# eight_neopixels.net
KiCad netlist of a schematic drawn in Altium Designer
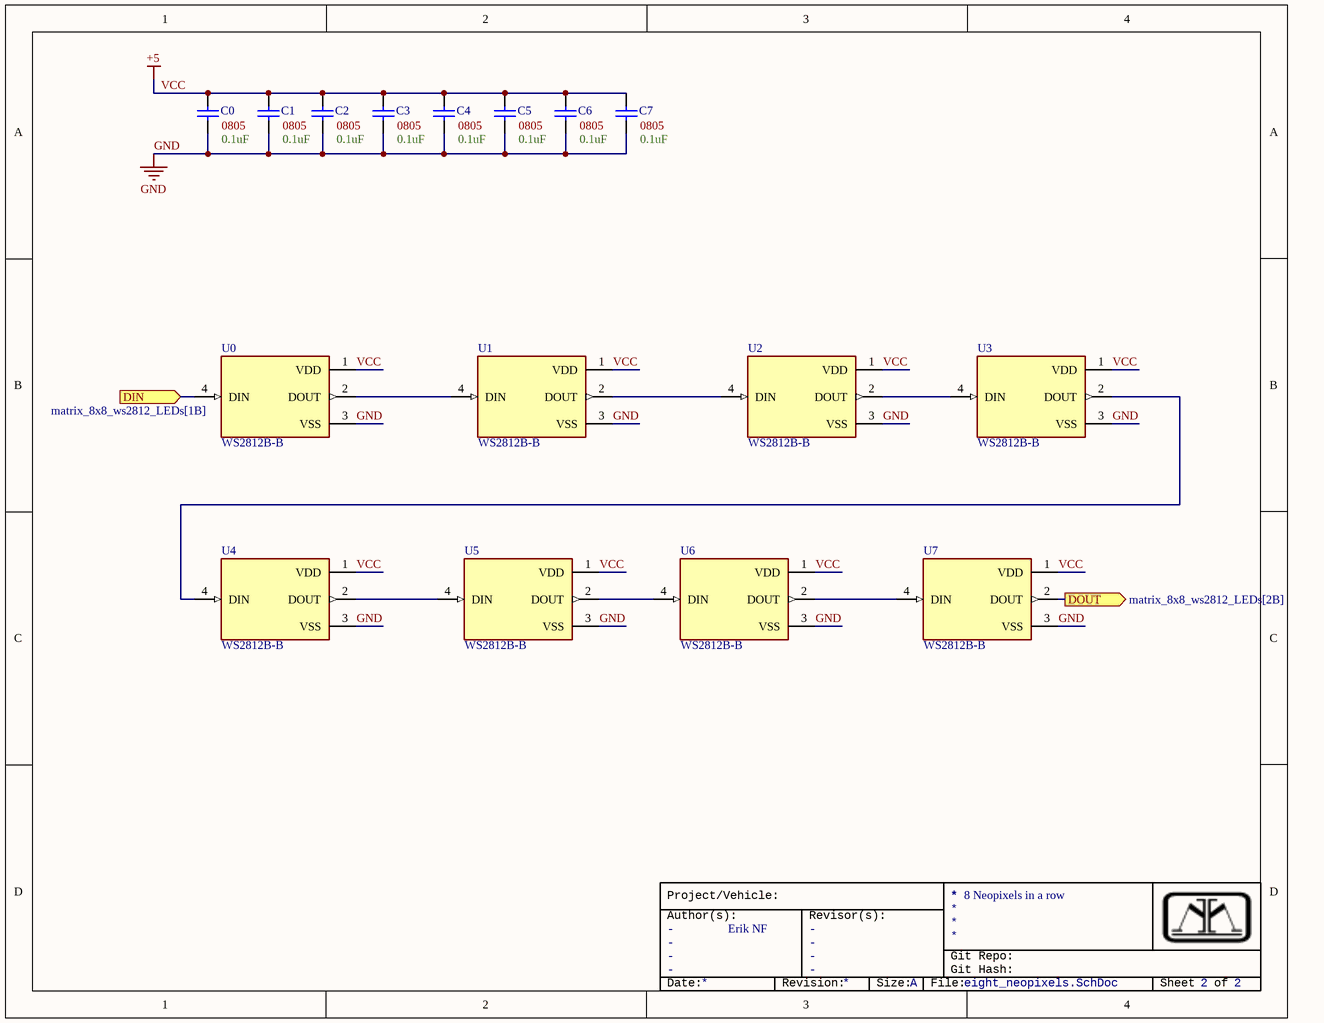
[diagram p0: eight_neopixels.SchDoc]

(export (version "E")
  (design (tool "Eeschema 10.0.6"))
  (components
    (comp (ref "C0")
      (value "SMD Nonpolarized")
      (footprint "[Cap] SMD 0805")
      (fields
        (field (name "VOLTAGE") "6.3V")
        (field (name "TOLERANCE") "10%")
        (field (name "SIZE PACKAGE") "0805")
        (field (name "CAPACITANCE") "0.1uF")
      )
      (libsource (lib "RADM Components") (part "[Cap] SMD Nonpolarized"))
    )
    (comp (ref "C1")
      (value "SMD Nonpolarized")
      (footprint "[Cap] SMD 0805")
      (fields
        (field (name "VOLTAGE") "6.3V")
        (field (name "TOLERANCE") "10%")
        (field (name "SIZE PACKAGE") "0805")
        (field (name "CAPACITANCE") "0.1uF")
      )
      (libsource (lib "RADM Components") (part "[Cap] SMD Nonpolarized"))
    )
    (comp (ref "C2")
      (value "SMD Nonpolarized")
      (footprint "[Cap] SMD 0805")
      (fields
        (field (name "VOLTAGE") "6.3V")
        (field (name "TOLERANCE") "10%")
        (field (name "SIZE PACKAGE") "0805")
        (field (name "CAPACITANCE") "0.1uF")
      )
      (libsource (lib "RADM Components") (part "[Cap] SMD Nonpolarized"))
    )
    (comp (ref "C3")
      (value "SMD Nonpolarized")
      (footprint "[Cap] SMD 0805")
      (fields
        (field (name "VOLTAGE") "6.3V")
        (field (name "TOLERANCE") "10%")
        (field (name "SIZE PACKAGE") "0805")
        (field (name "CAPACITANCE") "0.1uF")
      )
      (libsource (lib "RADM Components") (part "[Cap] SMD Nonpolarized"))
    )
    (comp (ref "C4")
      (value "SMD Nonpolarized")
      (footprint "[Cap] SMD 0805")
      (fields
        (field (name "VOLTAGE") "6.3V")
        (field (name "TOLERANCE") "10%")
        (field (name "SIZE PACKAGE") "0805")
        (field (name "CAPACITANCE") "0.1uF")
      )
      (libsource (lib "RADM Components") (part "[Cap] SMD Nonpolarized"))
    )
    (comp (ref "C5")
      (value "SMD Nonpolarized")
      (footprint "[Cap] SMD 0805")
      (fields
        (field (name "VOLTAGE") "6.3V")
        (field (name "TOLERANCE") "10%")
        (field (name "SIZE PACKAGE") "0805")
        (field (name "CAPACITANCE") "0.1uF")
      )
      (libsource (lib "RADM Components") (part "[Cap] SMD Nonpolarized"))
    )
    (comp (ref "C6")
      (value "SMD Nonpolarized")
      (footprint "[Cap] SMD 0805")
      (fields
        (field (name "VOLTAGE") "6.3V")
        (field (name "TOLERANCE") "10%")
        (field (name "SIZE PACKAGE") "0805")
        (field (name "CAPACITANCE") "0.1uF")
      )
      (libsource (lib "RADM Components") (part "[Cap] SMD Nonpolarized"))
    )
    (comp (ref "C7")
      (value "SMD Nonpolarized")
      (footprint "[Cap] SMD 0805")
      (fields
        (field (name "VOLTAGE") "6.3V")
        (field (name "TOLERANCE") "10%")
        (field (name "SIZE PACKAGE") "0805")
        (field (name "CAPACITANCE") "0.1uF")
      )
      (libsource (lib "RADM Components") (part "[Cap] SMD Nonpolarized"))
    )
    (comp (ref "U0")
      (value "WS2812B-B")
      (footprint "LED_WS2812B-B")
      (description "Intelligent control LED integrated light source")
      (libsource (lib "WS2812B-B") (part "WS2812B-B"))
    )
    (comp (ref "U1")
      (value "WS2812B-B")
      (footprint "LED_WS2812B-B")
      (description "Intelligent control LED integrated light source")
      (libsource (lib "WS2812B-B") (part "WS2812B-B"))
    )
    (comp (ref "U2")
      (value "WS2812B-B")
      (footprint "LED_WS2812B-B")
      (description "Intelligent control LED integrated light source")
      (libsource (lib "WS2812B-B") (part "WS2812B-B"))
    )
    (comp (ref "U3")
      (value "WS2812B-B")
      (footprint "LED_WS2812B-B")
      (description "Intelligent control LED integrated light source")
      (libsource (lib "WS2812B-B") (part "WS2812B-B"))
    )
    (comp (ref "U4")
      (value "WS2812B-B")
      (footprint "LED_WS2812B-B")
      (description "Intelligent control LED integrated light source")
      (libsource (lib "WS2812B-B") (part "WS2812B-B"))
    )
    (comp (ref "U5")
      (value "WS2812B-B")
      (footprint "LED_WS2812B-B")
      (description "Intelligent control LED integrated light source")
      (libsource (lib "WS2812B-B") (part "WS2812B-B"))
    )
    (comp (ref "U6")
      (value "WS2812B-B")
      (footprint "LED_WS2812B-B")
      (description "Intelligent control LED integrated light source")
      (libsource (lib "WS2812B-B") (part "WS2812B-B"))
    )
    (comp (ref "U7")
      (value "WS2812B-B")
      (footprint "LED_WS2812B-B")
      (description "Intelligent control LED integrated light source")
      (libsource (lib "WS2812B-B") (part "WS2812B-B"))
    )
  )
  (nets
    (net (code "1") (name "+5") (class "Default")
      (node (ref "C0") (pin "2") (pinfunction "2_2") (pintype "passive"))
      (node (ref "C1") (pin "2") (pinfunction "2_2") (pintype "passive"))
      (node (ref "C2") (pin "2") (pinfunction "2_2") (pintype "passive"))
      (node (ref "C3") (pin "2") (pinfunction "2_2") (pintype "passive"))
      (node (ref "C4") (pin "2") (pinfunction "2_2") (pintype "passive"))
      (node (ref "C5") (pin "2") (pinfunction "2_2") (pintype "passive"))
      (node (ref "C6") (pin "2") (pinfunction "2_2") (pintype "passive"))
      (node (ref "C7") (pin "2") (pinfunction "2_2") (pintype "passive"))
      (node (ref "U0") (pin "1") (pinfunction "VDD_1") (pintype "power_in"))
      (node (ref "U1") (pin "1") (pinfunction "VDD_1") (pintype "power_in"))
      (node (ref "U2") (pin "1") (pinfunction "VDD_1") (pintype "power_in"))
      (node (ref "U3") (pin "1") (pinfunction "VDD_1") (pintype "power_in"))
      (node (ref "U4") (pin "1") (pinfunction "VDD_1") (pintype "power_in"))
      (node (ref "U5") (pin "1") (pinfunction "VDD_1") (pintype "power_in"))
      (node (ref "U6") (pin "1") (pinfunction "VDD_1") (pintype "power_in"))
      (node (ref "U7") (pin "1") (pinfunction "VDD_1") (pintype "power_in"))
    )
    (net (code "2") (name "/DIN") (class "Default")
      (node (ref "U0") (pin "4") (pinfunction "DIN_4") (pintype "input"))
    )
    (net (code "3") (name "/DOUT") (class "Default")
      (node (ref "U7") (pin "2") (pinfunction "DOUT_2") (pintype "output"))
    )
    (net (code "4") (name "GND") (class "Default")
      (node (ref "C0") (pin "1") (pinfunction "1_1") (pintype "passive"))
      (node (ref "C1") (pin "1") (pinfunction "1_1") (pintype "passive"))
      (node (ref "C2") (pin "1") (pinfunction "1_1") (pintype "passive"))
      (node (ref "C3") (pin "1") (pinfunction "1_1") (pintype "passive"))
      (node (ref "C4") (pin "1") (pinfunction "1_1") (pintype "passive"))
      (node (ref "C5") (pin "1") (pinfunction "1_1") (pintype "passive"))
      (node (ref "C6") (pin "1") (pinfunction "1_1") (pintype "passive"))
      (node (ref "C7") (pin "1") (pinfunction "1_1") (pintype "passive"))
      (node (ref "U0") (pin "3") (pinfunction "VSS_3") (pintype "power_in"))
      (node (ref "U1") (pin "3") (pinfunction "VSS_3") (pintype "power_in"))
      (node (ref "U2") (pin "3") (pinfunction "VSS_3") (pintype "power_in"))
      (node (ref "U3") (pin "3") (pinfunction "VSS_3") (pintype "power_in"))
      (node (ref "U4") (pin "3") (pinfunction "VSS_3") (pintype "power_in"))
      (node (ref "U5") (pin "3") (pinfunction "VSS_3") (pintype "power_in"))
      (node (ref "U6") (pin "3") (pinfunction "VSS_3") (pintype "power_in"))
      (node (ref "U7") (pin "3") (pinfunction "VSS_3") (pintype "power_in"))
    )
    (net (code "5") (name "Net-(U0-DOUT)") (class "Default")
      (node (ref "U0") (pin "2") (pinfunction "DOUT_2") (pintype "output"))
      (node (ref "U1") (pin "4") (pinfunction "DIN_4") (pintype "input"))
    )
    (net (code "6") (name "Net-(U1-DOUT)") (class "Default")
      (node (ref "U1") (pin "2") (pinfunction "DOUT_2") (pintype "output"))
      (node (ref "U2") (pin "4") (pinfunction "DIN_4") (pintype "input"))
    )
    (net (code "7") (name "Net-(U2-DOUT)") (class "Default")
      (node (ref "U2") (pin "2") (pinfunction "DOUT_2") (pintype "output"))
      (node (ref "U3") (pin "4") (pinfunction "DIN_4") (pintype "input"))
    )
    (net (code "8") (name "Net-(U3-DOUT)") (class "Default")
      (node (ref "U3") (pin "2") (pinfunction "DOUT_2") (pintype "output"))
      (node (ref "U4") (pin "4") (pinfunction "DIN_4") (pintype "input"))
    )
    (net (code "9") (name "Net-(U4-DOUT)") (class "Default")
      (node (ref "U4") (pin "2") (pinfunction "DOUT_2") (pintype "output"))
      (node (ref "U5") (pin "4") (pinfunction "DIN_4") (pintype "input"))
    )
    (net (code "10") (name "Net-(U5-DOUT)") (class "Default")
      (node (ref "U5") (pin "2") (pinfunction "DOUT_2") (pintype "output"))
      (node (ref "U6") (pin "4") (pinfunction "DIN_4") (pintype "input"))
    )
    (net (code "11") (name "Net-(U6-DOUT)") (class "Default")
      (node (ref "U6") (pin "2") (pinfunction "DOUT_2") (pintype "output"))
      (node (ref "U7") (pin "4") (pinfunction "DIN_4") (pintype "input"))
    )
  )
)
